# 09_POWER.net
KiCad netlist of a schematic drawn in Altium Designer
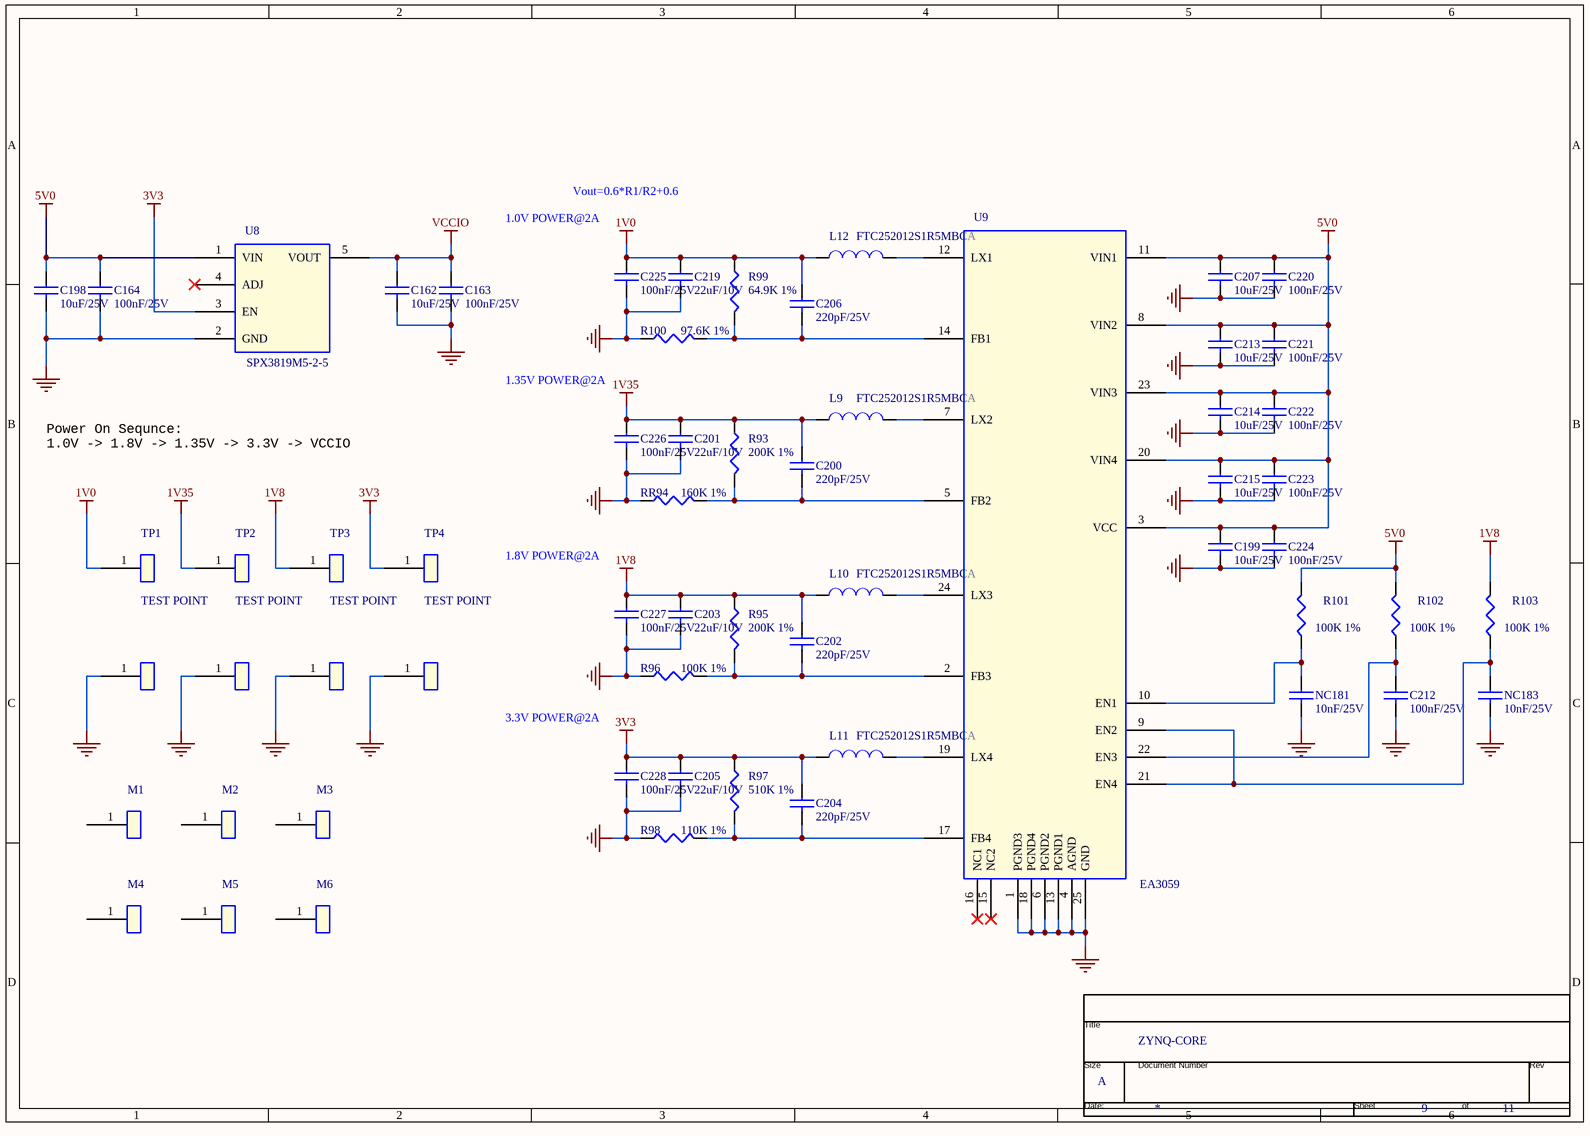
[diagram p0: 09_POWER.SchDoc]

(export (version "E")
  (design (tool "Eeschema 10.0.6"))
  (components
    (comp (ref "C162") (value "10uF/25V") (footprint "C0603") (libsource (lib "*") (part "CAP NP")))
    (comp (ref "C163") (value "100nF/25V") (footprint "C0402") (libsource (lib "*") (part "CAP NP")))
    (comp (ref "C164") (value "100nF/25V") (footprint "C0402") (libsource (lib "*") (part "CAP NP")))
    (comp (ref "C198") (value "10uF/25V") (footprint "C0603") (libsource (lib "*") (part "CAP NP")))
    (comp (ref "C199") (value "10uF/25V") (footprint "C0603") (libsource (lib "*") (part "CAP NP")))
    (comp (ref "C200") (value "220pF/25V") (footprint "C0402") (libsource (lib "*") (part "CAP NP")))
    (comp (ref "C201") (value "22uF/10V") (footprint "C0603") (libsource (lib "*") (part "CAP NP")))
    (comp (ref "C202") (value "220pF/25V") (footprint "C0402") (libsource (lib "*") (part "CAP NP")))
    (comp (ref "C203") (value "22uF/10V") (footprint "C0603") (libsource (lib "*") (part "CAP NP")))
    (comp (ref "C204") (value "220pF/25V") (footprint "C0402") (libsource (lib "*") (part "CAP NP")))
    (comp (ref "C205") (value "22uF/10V") (footprint "C0603") (libsource (lib "*") (part "CAP NP")))
    (comp (ref "C206") (value "220pF/25V") (footprint "C0402") (libsource (lib "*") (part "CAP NP")))
    (comp (ref "C207") (value "10uF/25V") (footprint "C0603") (libsource (lib "*") (part "CAP NP")))
    (comp (ref "C212")
      (value "100nF/25V")
      (footprint "C0603")
      (description "0603")
      (libsource (lib "*") (part "CAP NP"))
    )
    (comp (ref "C213") (value "10uF/25V") (footprint "C0603") (libsource (lib "*") (part "CAP NP")))
    (comp (ref "C214") (value "10uF/25V") (footprint "C0603") (libsource (lib "*") (part "CAP NP")))
    (comp (ref "C215") (value "10uF/25V") (footprint "C0603") (libsource (lib "*") (part "CAP NP")))
    (comp (ref "C219") (value "22uF/10V") (footprint "C0603") (libsource (lib "*") (part "CAP NP")))
    (comp (ref "C220") (value "100nF/25V") (footprint "C0402") (libsource (lib "*") (part "CAP NP")))
    (comp (ref "C221") (value "100nF/25V") (footprint "C0402") (libsource (lib "*") (part "CAP NP")))
    (comp (ref "C222") (value "100nF/25V") (footprint "C0402") (libsource (lib "*") (part "CAP NP")))
    (comp (ref "C223") (value "100nF/25V") (footprint "C0402") (libsource (lib "*") (part "CAP NP")))
    (comp (ref "C224") (value "100nF/25V") (footprint "C0402") (libsource (lib "*") (part "CAP NP")))
    (comp (ref "C225") (value "100nF/25V") (footprint "C0402") (libsource (lib "*") (part "CAP NP")))
    (comp (ref "C226") (value "100nF/25V") (footprint "C0402") (libsource (lib "*") (part "CAP NP")))
    (comp (ref "C227") (value "100nF/25V") (footprint "C0402") (libsource (lib "*") (part "CAP NP")))
    (comp (ref "C228") (value "100nF/25V") (footprint "C0402") (libsource (lib "*") (part "CAP NP")))
    (comp (ref "H1") (value "H1") (footprint "HOLE3_8D2_6MM") (libsource (lib "*") (part "TEST POINT")))
    (comp (ref "H2") (value "H2") (footprint "HOLE3_8D2_6MM") (libsource (lib "*") (part "TEST POINT")))
    (comp (ref "H3") (value "H3") (footprint "HOLE3_8D2_6MM") (libsource (lib "*") (part "TEST POINT")))
    (comp (ref "H4") (value "H4") (footprint "HOLE3_8D2_6MM") (libsource (lib "*") (part "TEST POINT")))
    (comp (ref "L9")
      (value "FTC252012S1R5MBCA")
      (footprint "2520")
      (description "1.5uH")
      (libsource (lib "*") (part "INDUCTOR"))
    )
    (comp (ref "L10")
      (value "FTC252012S1R5MBCA")
      (footprint "2520")
      (description "1.5uH")
      (libsource (lib "*") (part "INDUCTOR"))
    )
    (comp (ref "L11")
      (value "FTC252012S1R5MBCA")
      (footprint "2520")
      (description "1.5uH")
      (libsource (lib "*") (part "INDUCTOR"))
    )
    (comp (ref "L12")
      (value "FTC252012S1R5MBCA")
      (footprint "2520")
      (description "1.5uH")
      (libsource (lib "*") (part "INDUCTOR"))
    )
    (comp (ref "M1") (value "MARK") (footprint "Mark") (libsource (lib "*") (part "TEST POINT")))
    (comp (ref "M2") (value "MARK") (footprint "Mark") (libsource (lib "*") (part "TEST POINT")))
    (comp (ref "M3") (value "MARK") (footprint "Mark") (libsource (lib "*") (part "TEST POINT")))
    (comp (ref "M4") (value "MARK") (footprint "Mark") (libsource (lib "*") (part "TEST POINT")))
    (comp (ref "M5") (value "MARK") (footprint "Mark") (libsource (lib "*") (part "TEST POINT")))
    (comp (ref "M6") (value "MARK") (footprint "Mark") (libsource (lib "*") (part "TEST POINT")))
    (comp (ref "NC181") (value "10nF/25V") (footprint "C0603") (libsource (lib "*") (part "CAP NP")))
    (comp (ref "NC183") (value "10nF/25V") (footprint "C0603") (libsource (lib "*") (part "CAP NP")))
    (comp (ref "R93") (value "200K 1%") (footprint "R0402") (libsource (lib "*") (part "RESISTOR")))
    (comp (ref "R95") (value "200K 1%") (footprint "R0402") (libsource (lib "*") (part "RESISTOR")))
    (comp (ref "R96") (value "100K 1%") (footprint "R0402") (libsource (lib "*") (part "RESISTOR")))
    (comp (ref "R97") (value "510K 1%") (footprint "R0402") (libsource (lib "*") (part "RESISTOR")))
    (comp (ref "R98") (value "110K 1%") (footprint "R0402") (libsource (lib "*") (part "RESISTOR")))
    (comp (ref "R99") (value "64.9K 1%") (footprint "R0402") (libsource (lib "*") (part "RESISTOR")))
    (comp (ref "R100") (value "97.6K 1%") (footprint "R0402") (libsource (lib "*") (part "RESISTOR")))
    (comp (ref "R101") (value "100K 1%") (footprint "R0402") (libsource (lib "*") (part "RESISTOR")))
    (comp (ref "R102") (value "100K 1%") (footprint "R0402") (libsource (lib "*") (part "RESISTOR")))
    (comp (ref "R103") (value "100K 1%") (footprint "R0402") (libsource (lib "*") (part "RESISTOR")))
    (comp (ref "RR94") (value "160K 1%") (footprint "R0402") (libsource (lib "*") (part "RESISTOR")))
    (comp (ref "TP1") (value "TEST POINT") (footprint "FPAD_1") (libsource (lib "*") (part "TEST POINT")))
    (comp (ref "TP2") (value "TEST POINT") (footprint "FPAD_1") (libsource (lib "*") (part "TEST POINT")))
    (comp (ref "TP3") (value "TEST POINT") (footprint "FPAD_1") (libsource (lib "*") (part "TEST POINT")))
    (comp (ref "TP4") (value "TEST POINT") (footprint "FPAD_1") (libsource (lib "*") (part "TEST POINT")))
    (comp (ref "U8")
      (value "SPX3819M5-2-5")
      (footprint "SOT-23-5")
      (libsource (lib "*") (part "SPX3819M5-2-5"))
    )
    (comp (ref "U9") (value "EA3059") (footprint "QFN24_RTW") (libsource (lib "*") (part "EA3059")))
  )
  (nets
    (net (code "1") (name "1V0") (class "Default")
      (node (ref "C206") (pin "1") (pinfunction "1_1") (pintype "passive"))
      (node (ref "C219") (pin "1") (pinfunction "1_1") (pintype "passive"))
      (node (ref "C225") (pin "1") (pinfunction "1_1") (pintype "passive"))
      (node (ref "L12") (pin "1") (pinfunction "1_1") (pintype "passive"))
      (node (ref "R99") (pin "1") (pinfunction "1_1") (pintype "passive"))
      (node (ref "TP1") (pin "1") (pinfunction "1_1") (pintype "passive"))
    )
    (net (code "2") (name "1V8") (class "Default")
      (node (ref "C202") (pin "1") (pinfunction "1_1") (pintype "passive"))
      (node (ref "C203") (pin "1") (pinfunction "1_1") (pintype "passive"))
      (node (ref "C227") (pin "1") (pinfunction "1_1") (pintype "passive"))
      (node (ref "L10") (pin "1") (pinfunction "1_1") (pintype "passive"))
      (node (ref "R103") (pin "2") (pinfunction "2_2") (pintype "passive"))
      (node (ref "R95") (pin "1") (pinfunction "1_1") (pintype "passive"))
      (node (ref "TP3") (pin "1") (pinfunction "1_1") (pintype "passive"))
    )
    (net (code "3") (name "1V35") (class "Default")
      (node (ref "C200") (pin "1") (pinfunction "1_1") (pintype "passive"))
      (node (ref "C201") (pin "1") (pinfunction "1_1") (pintype "passive"))
      (node (ref "C226") (pin "1") (pinfunction "1_1") (pintype "passive"))
      (node (ref "L9") (pin "1") (pinfunction "1_1") (pintype "passive"))
      (node (ref "R93") (pin "1") (pinfunction "1_1") (pintype "passive"))
      (node (ref "TP2") (pin "1") (pinfunction "1_1") (pintype "passive"))
    )
    (net (code "4") (name "3V3") (class "Default")
      (node (ref "C204") (pin "1") (pinfunction "1_1") (pintype "passive"))
      (node (ref "C205") (pin "1") (pinfunction "1_1") (pintype "passive"))
      (node (ref "C228") (pin "1") (pinfunction "1_1") (pintype "passive"))
      (node (ref "L11") (pin "1") (pinfunction "1_1") (pintype "passive"))
      (node (ref "R97") (pin "1") (pinfunction "1_1") (pintype "passive"))
      (node (ref "TP4") (pin "1") (pinfunction "1_1") (pintype "passive"))
      (node (ref "U8") (pin "3") (pinfunction "EN_3") (pintype "passive"))
    )
    (net (code "5") (name "5V0") (class "Default")
      (node (ref "C164") (pin "1") (pinfunction "1_1") (pintype "passive"))
      (node (ref "C198") (pin "1") (pinfunction "1_1") (pintype "passive"))
      (node (ref "C199") (pin "1") (pinfunction "1_1") (pintype "passive"))
      (node (ref "C207") (pin "1") (pinfunction "1_1") (pintype "passive"))
      (node (ref "C213") (pin "1") (pinfunction "1_1") (pintype "passive"))
      (node (ref "C214") (pin "1") (pinfunction "1_1") (pintype "passive"))
      (node (ref "C215") (pin "1") (pinfunction "1_1") (pintype "passive"))
      (node (ref "C220") (pin "1") (pinfunction "1_1") (pintype "passive"))
      (node (ref "C221") (pin "1") (pinfunction "1_1") (pintype "passive"))
      (node (ref "C222") (pin "1") (pinfunction "1_1") (pintype "passive"))
      (node (ref "C223") (pin "1") (pinfunction "1_1") (pintype "passive"))
      (node (ref "C224") (pin "1") (pinfunction "1_1") (pintype "passive"))
      (node (ref "R101") (pin "2") (pinfunction "2_2") (pintype "passive"))
      (node (ref "R102") (pin "2") (pinfunction "2_2") (pintype "passive"))
      (node (ref "U8") (pin "1") (pinfunction "VIN_1") (pintype "passive"))
      (node (ref "U9") (pin "11") (pinfunction "VIN1_11") (pintype "passive"))
      (node (ref "U9") (pin "20") (pinfunction "VIN4_20") (pintype "passive"))
      (node (ref "U9") (pin "23") (pinfunction "VIN3_23") (pintype "passive"))
      (node (ref "U9") (pin "3") (pinfunction "VCC_3") (pintype "passive"))
      (node (ref "U9") (pin "8") (pinfunction "VIN2_8") (pintype "passive"))
    )
    (net (code "6") (name "GND") (class "Default")
      (node (ref "C162") (pin "2") (pinfunction "2_2") (pintype "passive"))
      (node (ref "C163") (pin "2") (pinfunction "2_2") (pintype "passive"))
      (node (ref "C164") (pin "2") (pinfunction "2_2") (pintype "passive"))
      (node (ref "C198") (pin "2") (pinfunction "2_2") (pintype "passive"))
      (node (ref "C199") (pin "2") (pinfunction "2_2") (pintype "passive"))
      (node (ref "C201") (pin "2") (pinfunction "2_2") (pintype "passive"))
      (node (ref "C203") (pin "2") (pinfunction "2_2") (pintype "passive"))
      (node (ref "C205") (pin "2") (pinfunction "2_2") (pintype "passive"))
      (node (ref "C207") (pin "2") (pinfunction "2_2") (pintype "passive"))
      (node (ref "C212") (pin "2") (pinfunction "2_2") (pintype "passive"))
      (node (ref "C213") (pin "2") (pinfunction "2_2") (pintype "passive"))
      (node (ref "C214") (pin "2") (pinfunction "2_2") (pintype "passive"))
      (node (ref "C215") (pin "2") (pinfunction "2_2") (pintype "passive"))
      (node (ref "C219") (pin "2") (pinfunction "2_2") (pintype "passive"))
      (node (ref "C220") (pin "2") (pinfunction "2_2") (pintype "passive"))
      (node (ref "C221") (pin "2") (pinfunction "2_2") (pintype "passive"))
      (node (ref "C222") (pin "2") (pinfunction "2_2") (pintype "passive"))
      (node (ref "C223") (pin "2") (pinfunction "2_2") (pintype "passive"))
      (node (ref "C224") (pin "2") (pinfunction "2_2") (pintype "passive"))
      (node (ref "C225") (pin "2") (pinfunction "2_2") (pintype "passive"))
      (node (ref "C226") (pin "2") (pinfunction "2_2") (pintype "passive"))
      (node (ref "C227") (pin "2") (pinfunction "2_2") (pintype "passive"))
      (node (ref "C228") (pin "2") (pinfunction "2_2") (pintype "passive"))
      (node (ref "H1") (pin "1") (pinfunction "1_1") (pintype "passive"))
      (node (ref "H2") (pin "1") (pinfunction "1_1") (pintype "passive"))
      (node (ref "H3") (pin "1") (pinfunction "1_1") (pintype "passive"))
      (node (ref "H4") (pin "1") (pinfunction "1_1") (pintype "passive"))
      (node (ref "NC181") (pin "2") (pinfunction "2_2") (pintype "passive"))
      (node (ref "NC183") (pin "2") (pinfunction "2_2") (pintype "passive"))
      (node (ref "R100") (pin "1") (pinfunction "1_1") (pintype "passive"))
      (node (ref "R96") (pin "1") (pinfunction "1_1") (pintype "passive"))
      (node (ref "R98") (pin "1") (pinfunction "1_1") (pintype "passive"))
      (node (ref "RR94") (pin "1") (pinfunction "1_1") (pintype "passive"))
      (node (ref "U8") (pin "2") (pinfunction "GND_2") (pintype "passive"))
      (node (ref "U9") (pin "1") (pinfunction "PGND3_1") (pintype "passive"))
      (node (ref "U9") (pin "13") (pinfunction "PGND1_13") (pintype "passive"))
      (node (ref "U9") (pin "18") (pinfunction "PGND4_18") (pintype "passive"))
      (node (ref "U9") (pin "25") (pinfunction "GND_25") (pintype "passive"))
      (node (ref "U9") (pin "4") (pinfunction "AGND_4") (pintype "passive"))
      (node (ref "U9") (pin "6") (pinfunction "PGND2_6") (pintype "passive"))
    )
    (net (code "7") (name "Net-(U9-EN1)") (class "Default")
      (node (ref "NC181") (pin "1") (pinfunction "1_1") (pintype "passive"))
      (node (ref "R101") (pin "1") (pinfunction "1_1") (pintype "passive"))
      (node (ref "U9") (pin "10") (pinfunction "EN1_10") (pintype "passive"))
    )
    (net (code "8") (name "Net-(U9-EN2)") (class "Default")
      (node (ref "NC183") (pin "1") (pinfunction "1_1") (pintype "passive"))
      (node (ref "R103") (pin "1") (pinfunction "1_1") (pintype "passive"))
      (node (ref "U9") (pin "21") (pinfunction "EN4_21") (pintype "passive"))
      (node (ref "U9") (pin "9") (pinfunction "EN2_9") (pintype "passive"))
    )
    (net (code "9") (name "Net-(U9-EN3)") (class "Default")
      (node (ref "C212") (pin "1") (pinfunction "1_1") (pintype "passive"))
      (node (ref "R102") (pin "1") (pinfunction "1_1") (pintype "passive"))
      (node (ref "U9") (pin "22") (pinfunction "EN3_22") (pintype "passive"))
    )
    (net (code "10") (name "Net-(U9-FB1)") (class "Default")
      (node (ref "C206") (pin "2") (pinfunction "2_2") (pintype "passive"))
      (node (ref "R100") (pin "2") (pinfunction "2_2") (pintype "passive"))
      (node (ref "R99") (pin "2") (pinfunction "2_2") (pintype "passive"))
      (node (ref "U9") (pin "14") (pinfunction "FB1_14") (pintype "passive"))
    )
    (net (code "11") (name "Net-(U9-FB2)") (class "Default")
      (node (ref "C200") (pin "2") (pinfunction "2_2") (pintype "passive"))
      (node (ref "R93") (pin "2") (pinfunction "2_2") (pintype "passive"))
      (node (ref "RR94") (pin "2") (pinfunction "2_2") (pintype "passive"))
      (node (ref "U9") (pin "5") (pinfunction "FB2_5") (pintype "passive"))
    )
    (net (code "12") (name "Net-(U9-FB3)") (class "Default")
      (node (ref "C202") (pin "2") (pinfunction "2_2") (pintype "passive"))
      (node (ref "R95") (pin "2") (pinfunction "2_2") (pintype "passive"))
      (node (ref "R96") (pin "2") (pinfunction "2_2") (pintype "passive"))
      (node (ref "U9") (pin "2") (pinfunction "FB3_2") (pintype "passive"))
    )
    (net (code "13") (name "Net-(U9-FB4)") (class "Default")
      (node (ref "C204") (pin "2") (pinfunction "2_2") (pintype "passive"))
      (node (ref "R97") (pin "2") (pinfunction "2_2") (pintype "passive"))
      (node (ref "R98") (pin "2") (pinfunction "2_2") (pintype "passive"))
      (node (ref "U9") (pin "17") (pinfunction "FB4_17") (pintype "passive"))
    )
    (net (code "14") (name "Net-(U9-LX1)") (class "Default")
      (node (ref "L12") (pin "2") (pinfunction "2_2") (pintype "passive"))
      (node (ref "U9") (pin "12") (pinfunction "LX1_12") (pintype "passive"))
    )
    (net (code "15") (name "Net-(U9-LX2)") (class "Default")
      (node (ref "L9") (pin "2") (pinfunction "2_2") (pintype "passive"))
      (node (ref "U9") (pin "7") (pinfunction "LX2_7") (pintype "passive"))
    )
    (net (code "16") (name "Net-(U9-LX3)") (class "Default")
      (node (ref "L10") (pin "2") (pinfunction "2_2") (pintype "passive"))
      (node (ref "U9") (pin "24") (pinfunction "LX3_24") (pintype "passive"))
    )
    (net (code "17") (name "Net-(U9-LX4)") (class "Default")
      (node (ref "L11") (pin "2") (pinfunction "2_2") (pintype "passive"))
      (node (ref "U9") (pin "19") (pinfunction "LX4_19") (pintype "passive"))
    )
    (net (code "18") (name "VCCIO") (class "Default")
      (node (ref "C162") (pin "1") (pinfunction "1_1") (pintype "passive"))
      (node (ref "C163") (pin "1") (pinfunction "1_1") (pintype "passive"))
      (node (ref "U8") (pin "5") (pinfunction "VOUT_5") (pintype "passive"))
    )
    (net (code "19") (name "unconnected-(M1-Pad1)") (class "Default")
      (node (ref "M1") (pin "1") (pinfunction "1_1") (pintype "passive"))
    )
    (net (code "20") (name "unconnected-(M2-Pad1)") (class "Default")
      (node (ref "M2") (pin "1") (pinfunction "1_1") (pintype "passive"))
    )
    (net (code "21") (name "unconnected-(M3-Pad1)") (class "Default")
      (node (ref "M3") (pin "1") (pinfunction "1_1") (pintype "passive"))
    )
    (net (code "22") (name "unconnected-(M4-Pad1)") (class "Default")
      (node (ref "M4") (pin "1") (pinfunction "1_1") (pintype "passive"))
    )
    (net (code "23") (name "unconnected-(M5-Pad1)") (class "Default")
      (node (ref "M5") (pin "1") (pinfunction "1_1") (pintype "passive"))
    )
    (net (code "24") (name "unconnected-(M6-Pad1)") (class "Default")
      (node (ref "M6") (pin "1") (pinfunction "1_1") (pintype "passive"))
    )
    (net (code "25") (name "unconnected-(U8-ADJ-Pad4)") (class "Default")
      (node (ref "U8") (pin "4") (pinfunction "ADJ_4") (pintype "passive+no_connect"))
    )
    (net (code "26") (name "unconnected-(U9-NC1-Pad16)") (class "Default")
      (node (ref "U9") (pin "16") (pinfunction "NC1_16") (pintype "passive+no_connect"))
    )
    (net (code "27") (name "unconnected-(U9-NC2-Pad15)") (class "Default")
      (node (ref "U9") (pin "15") (pinfunction "NC2_15") (pintype "passive+no_connect"))
    )
  )
)
